# ADC_Input.net
KiCad netlist of a schematic drawn in Altium Designer
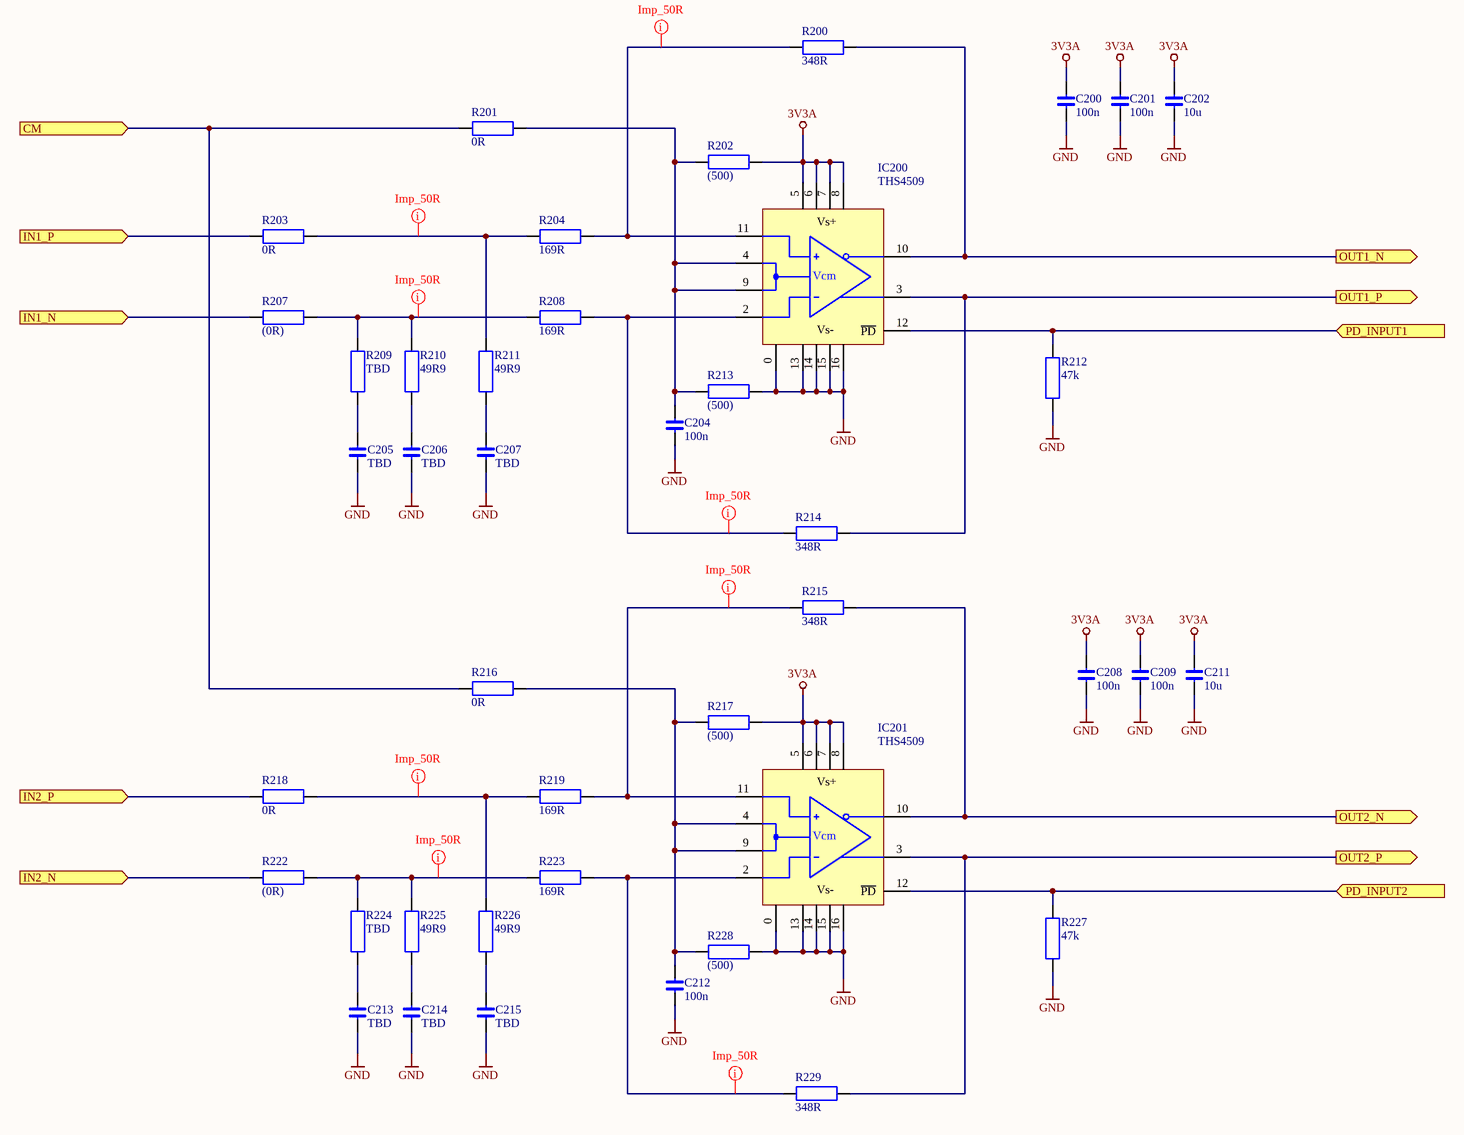
[diagram p0: ADC_Input.SchDoc]

(export (version "E")
  (design (tool "Eeschema 10.0.6"))
  (components
    (comp (ref "C200")
      (value "100n")
      (footprint "0603 SMALL OUTLINE")
      (description "C")
      (libsource (lib "RCL") (part "C"))
    )
    (comp (ref "C201")
      (value "100n")
      (footprint "0603 SMALL OUTLINE")
      (description "C")
      (libsource (lib "RCL") (part "C"))
    )
    (comp (ref "C202")
      (value "10u")
      (footprint "0805 SMALL OUTLINE")
      (description "C")
      (libsource (lib "RCL") (part "C"))
    )
    (comp (ref "C204")
      (value "100n")
      (footprint "0603 SMALL OUTLINE")
      (description "C")
      (libsource (lib "RCL") (part "C"))
    )
    (comp (ref "C205")
      (value "TBD")
      (footprint "0603 SMALL OUTLINE")
      (description "C")
      (libsource (lib "RCL") (part "C"))
    )
    (comp (ref "C206")
      (value "TBD")
      (footprint "0603 SMALL OUTLINE")
      (description "C")
      (libsource (lib "RCL") (part "C"))
    )
    (comp (ref "C207")
      (value "TBD")
      (footprint "0603 SMALL OUTLINE")
      (description "C")
      (libsource (lib "RCL") (part "C"))
    )
    (comp (ref "C208")
      (value "100n")
      (footprint "0603 SMALL OUTLINE")
      (description "C")
      (libsource (lib "RCL") (part "C"))
    )
    (comp (ref "C209")
      (value "100n")
      (footprint "0603 SMALL OUTLINE")
      (description "C")
      (libsource (lib "RCL") (part "C"))
    )
    (comp (ref "C211")
      (value "10u")
      (footprint "0805 SMALL OUTLINE")
      (description "C")
      (libsource (lib "RCL") (part "C"))
    )
    (comp (ref "C212")
      (value "100n")
      (footprint "0603 SMALL OUTLINE")
      (description "C")
      (libsource (lib "RCL") (part "C"))
    )
    (comp (ref "C213")
      (value "TBD")
      (footprint "0603 SMALL OUTLINE")
      (description "C")
      (libsource (lib "RCL") (part "C"))
    )
    (comp (ref "C214")
      (value "TBD")
      (footprint "0603 SMALL OUTLINE")
      (description "C")
      (libsource (lib "RCL") (part "C"))
    )
    (comp (ref "C215")
      (value "TBD")
      (footprint "0603 SMALL OUTLINE")
      (description "C")
      (libsource (lib "RCL") (part "C"))
    )
    (comp (ref "IC200")
      (value "THS4509")
      (footprint "QFN16_LONG")
      (description "WIDEBAND, LOW-NOISE, LOW-DISTORTION, FULLY-DIFFERENTIAL AMPLIFIER")
      (libsource (lib "Private") (part "THS4509"))
    )
    (comp (ref "IC201")
      (value "THS4509")
      (footprint "QFN16_LONG")
      (description "WIDEBAND, LOW-NOISE, LOW-DISTORTION, FULLY-DIFFERENTIAL AMPLIFIER")
      (libsource (lib "Private") (part "THS4509"))
    )
    (comp (ref "R200")
      (value "348R")
      (footprint "0603 SMALL OUTLINE")
      (description "R")
      (libsource (lib "RCL") (part "R"))
    )
    (comp (ref "R201")
      (value "0R")
      (footprint "0603 SMALL OUTLINE")
      (description "R")
      (libsource (lib "RCL") (part "R"))
    )
    (comp (ref "R202")
      (value "(500)")
      (footprint "0603 SMALL OUTLINE")
      (description "R")
      (libsource (lib "RCL") (part "R"))
    )
    (comp (ref "R203")
      (value "0R")
      (footprint "0603 SMALL OUTLINE")
      (description "R")
      (libsource (lib "RCL") (part "R"))
    )
    (comp (ref "R204")
      (value "169R")
      (footprint "0603 SMALL OUTLINE")
      (description "R")
      (libsource (lib "RCL") (part "R"))
    )
    (comp (ref "R207")
      (value "(0R)")
      (footprint "0603 SMALL OUTLINE")
      (description "R")
      (libsource (lib "RCL") (part "R"))
    )
    (comp (ref "R208")
      (value "169R")
      (footprint "0603 SMALL OUTLINE")
      (description "R")
      (libsource (lib "RCL") (part "R"))
    )
    (comp (ref "R209")
      (value "TBD")
      (footprint "0603 SMALL OUTLINE")
      (description "R")
      (libsource (lib "RCL") (part "R"))
    )
    (comp (ref "R210")
      (value "49R9")
      (footprint "0603 SMALL OUTLINE")
      (description "R")
      (libsource (lib "RCL") (part "R"))
    )
    (comp (ref "R211")
      (value "49R9")
      (footprint "0603 SMALL OUTLINE")
      (description "R")
      (libsource (lib "RCL") (part "R"))
    )
    (comp (ref "R212")
      (value "47k")
      (footprint "0603 SMALL OUTLINE")
      (description "R")
      (libsource (lib "RCL") (part "R"))
    )
    (comp (ref "R213")
      (value "(500)")
      (footprint "0603 SMALL OUTLINE")
      (description "R")
      (libsource (lib "RCL") (part "R"))
    )
    (comp (ref "R214")
      (value "348R")
      (footprint "0603 SMALL OUTLINE")
      (description "R")
      (libsource (lib "RCL") (part "R"))
    )
    (comp (ref "R215")
      (value "348R")
      (footprint "0603 SMALL OUTLINE")
      (description "R")
      (libsource (lib "RCL") (part "R"))
    )
    (comp (ref "R216")
      (value "0R")
      (footprint "0603 SMALL OUTLINE")
      (description "R")
      (libsource (lib "RCL") (part "R"))
    )
    (comp (ref "R217")
      (value "(500)")
      (footprint "0603 SMALL OUTLINE")
      (description "R")
      (libsource (lib "RCL") (part "R"))
    )
    (comp (ref "R218")
      (value "0R")
      (footprint "0603 SMALL OUTLINE")
      (description "R")
      (libsource (lib "RCL") (part "R"))
    )
    (comp (ref "R219")
      (value "169R")
      (footprint "0603 SMALL OUTLINE")
      (description "R")
      (libsource (lib "RCL") (part "R"))
    )
    (comp (ref "R222")
      (value "(0R)")
      (footprint "0603 SMALL OUTLINE")
      (description "R")
      (libsource (lib "RCL") (part "R"))
    )
    (comp (ref "R223")
      (value "169R")
      (footprint "0603 SMALL OUTLINE")
      (description "R")
      (libsource (lib "RCL") (part "R"))
    )
    (comp (ref "R224")
      (value "TBD")
      (footprint "0603 SMALL OUTLINE")
      (description "R")
      (libsource (lib "RCL") (part "R"))
    )
    (comp (ref "R225")
      (value "49R9")
      (footprint "0603 SMALL OUTLINE")
      (description "R")
      (libsource (lib "RCL") (part "R"))
    )
    (comp (ref "R226")
      (value "49R9")
      (footprint "0603 SMALL OUTLINE")
      (description "R")
      (libsource (lib "RCL") (part "R"))
    )
    (comp (ref "R227")
      (value "47k")
      (footprint "0603 SMALL OUTLINE")
      (description "R")
      (libsource (lib "RCL") (part "R"))
    )
    (comp (ref "R228")
      (value "(500)")
      (footprint "0603 SMALL OUTLINE")
      (description "R")
      (libsource (lib "RCL") (part "R"))
    )
    (comp (ref "R229")
      (value "348R")
      (footprint "0603 SMALL OUTLINE")
      (description "R")
      (libsource (lib "RCL") (part "R"))
    )
  )
  (nets
    (net (code "1") (name "/CM") (class "Default")
      (node (ref "R201") (pin "1") (pinfunction "1_1") (pintype "passive"))
      (node (ref "R216") (pin "1") (pinfunction "1_1") (pintype "passive"))
    )
    (net (code "2") (name "/IN1_N") (class "Default")
      (node (ref "R207") (pin "1") (pinfunction "1_1") (pintype "passive"))
    )
    (net (code "3") (name "/IN1_P") (class "Default")
      (node (ref "R203") (pin "1") (pinfunction "1_1") (pintype "passive"))
    )
    (net (code "4") (name "/IN2_N") (class "Default")
      (node (ref "R222") (pin "1") (pinfunction "1_1") (pintype "passive"))
    )
    (net (code "5") (name "/IN2_P") (class "Default")
      (node (ref "R218") (pin "1") (pinfunction "1_1") (pintype "passive"))
    )
    (net (code "6") (name "/OUT1_N") (class "Default")
      (node (ref "IC200") (pin "10") (pinfunction "-OUT_10") (pintype "passive"))
      (node (ref "R200") (pin "1") (pinfunction "1_1") (pintype "passive"))
    )
    (net (code "7") (name "/OUT1_P") (class "Default")
      (node (ref "IC200") (pin "3") (pinfunction "+OUT_3") (pintype "passive"))
      (node (ref "R214") (pin "1") (pinfunction "1_1") (pintype "passive"))
    )
    (net (code "8") (name "/OUT2_N") (class "Default")
      (node (ref "IC201") (pin "10") (pinfunction "-OUT_10") (pintype "passive"))
      (node (ref "R215") (pin "1") (pinfunction "1_1") (pintype "passive"))
    )
    (net (code "9") (name "/OUT2_P") (class "Default")
      (node (ref "IC201") (pin "3") (pinfunction "+OUT_3") (pintype "passive"))
      (node (ref "R229") (pin "1") (pinfunction "1_1") (pintype "passive"))
    )
    (net (code "10") (name "/PD_INPUT1") (class "Default")
      (node (ref "IC200") (pin "12") (pinfunction "~{PD}_12") (pintype "passive"))
      (node (ref "R212") (pin "2") (pinfunction "2_2") (pintype "passive"))
    )
    (net (code "11") (name "/PD_INPUT2") (class "Default")
      (node (ref "IC201") (pin "12") (pinfunction "~{PD}_12") (pintype "passive"))
      (node (ref "R227") (pin "2") (pinfunction "2_2") (pintype "passive"))
    )
    (net (code "12") (name "3V3A") (class "Default")
      (node (ref "C200") (pin "1") (pinfunction "1_1") (pintype "passive"))
      (node (ref "C201") (pin "1") (pinfunction "1_1") (pintype "passive"))
      (node (ref "C202") (pin "1") (pinfunction "1_1") (pintype "passive"))
      (node (ref "C208") (pin "1") (pinfunction "1_1") (pintype "passive"))
      (node (ref "C209") (pin "1") (pinfunction "1_1") (pintype "passive"))
      (node (ref "C211") (pin "1") (pinfunction "1_1") (pintype "passive"))
      (node (ref "IC200") (pin "5") (pinfunction "Vs+_5") (pintype "passive"))
      (node (ref "IC200") (pin "6") (pinfunction "Vs+_6") (pintype "passive"))
      (node (ref "IC200") (pin "7") (pinfunction "Vs+_7") (pintype "passive"))
      (node (ref "IC200") (pin "8") (pinfunction "Vs+_8") (pintype "passive"))
      (node (ref "IC201") (pin "5") (pinfunction "Vs+_5") (pintype "passive"))
      (node (ref "IC201") (pin "6") (pinfunction "Vs+_6") (pintype "passive"))
      (node (ref "IC201") (pin "7") (pinfunction "Vs+_7") (pintype "passive"))
      (node (ref "IC201") (pin "8") (pinfunction "Vs+_8") (pintype "passive"))
      (node (ref "R202") (pin "1") (pinfunction "1_1") (pintype "passive"))
      (node (ref "R217") (pin "1") (pinfunction "1_1") (pintype "passive"))
    )
    (net (code "13") (name "GND") (class "Default")
      (node (ref "C200") (pin "2") (pinfunction "2_2") (pintype "passive"))
      (node (ref "C201") (pin "2") (pinfunction "2_2") (pintype "passive"))
      (node (ref "C202") (pin "2") (pinfunction "2_2") (pintype "passive"))
      (node (ref "C204") (pin "2") (pinfunction "2_2") (pintype "passive"))
      (node (ref "C205") (pin "2") (pinfunction "2_2") (pintype "passive"))
      (node (ref "C206") (pin "2") (pinfunction "2_2") (pintype "passive"))
      (node (ref "C207") (pin "2") (pinfunction "2_2") (pintype "passive"))
      (node (ref "C208") (pin "2") (pinfunction "2_2") (pintype "passive"))
      (node (ref "C209") (pin "2") (pinfunction "2_2") (pintype "passive"))
      (node (ref "C211") (pin "2") (pinfunction "2_2") (pintype "passive"))
      (node (ref "C212") (pin "2") (pinfunction "2_2") (pintype "passive"))
      (node (ref "C213") (pin "2") (pinfunction "2_2") (pintype "passive"))
      (node (ref "C214") (pin "2") (pinfunction "2_2") (pintype "passive"))
      (node (ref "C215") (pin "2") (pinfunction "2_2") (pintype "passive"))
      (node (ref "IC200") (pin "0") (pinfunction "PAD_0") (pintype "passive"))
      (node (ref "IC200") (pin "13") (pinfunction "Vs-_13") (pintype "passive"))
      (node (ref "IC200") (pin "14") (pinfunction "Vs-_14") (pintype "passive"))
      (node (ref "IC200") (pin "15") (pinfunction "Vs-_15") (pintype "passive"))
      (node (ref "IC200") (pin "16") (pinfunction "Vs-_16") (pintype "passive"))
      (node (ref "IC201") (pin "0") (pinfunction "PAD_0") (pintype "passive"))
      (node (ref "IC201") (pin "13") (pinfunction "Vs-_13") (pintype "passive"))
      (node (ref "IC201") (pin "14") (pinfunction "Vs-_14") (pintype "passive"))
      (node (ref "IC201") (pin "15") (pinfunction "Vs-_15") (pintype "passive"))
      (node (ref "IC201") (pin "16") (pinfunction "Vs-_16") (pintype "passive"))
      (node (ref "R212") (pin "1") (pinfunction "1_1") (pintype "passive"))
      (node (ref "R213") (pin "1") (pinfunction "1_1") (pintype "passive"))
      (node (ref "R227") (pin "1") (pinfunction "1_1") (pintype "passive"))
      (node (ref "R228") (pin "1") (pinfunction "1_1") (pintype "passive"))
    )
    (net (code "14") (name "Net-(C204-Pad1)") (class "Default")
      (node (ref "C204") (pin "1") (pinfunction "1_1") (pintype "passive"))
      (node (ref "IC200") (pin "4") (pinfunction "CM_4") (pintype "passive"))
      (node (ref "IC200") (pin "9") (pinfunction "CM_9") (pintype "passive"))
      (node (ref "R201") (pin "2") (pinfunction "2_2") (pintype "passive"))
      (node (ref "R202") (pin "2") (pinfunction "2_2") (pintype "passive"))
      (node (ref "R213") (pin "2") (pinfunction "2_2") (pintype "passive"))
    )
    (net (code "15") (name "Net-(C205-Pad1)") (class "Default")
      (node (ref "C205") (pin "1") (pinfunction "1_1") (pintype "passive"))
      (node (ref "R209") (pin "1") (pinfunction "1_1") (pintype "passive"))
    )
    (net (code "16") (name "Net-(C206-Pad1)") (class "Default")
      (node (ref "C206") (pin "1") (pinfunction "1_1") (pintype "passive"))
      (node (ref "R210") (pin "1") (pinfunction "1_1") (pintype "passive"))
    )
    (net (code "17") (name "Net-(C207-Pad1)") (class "Default")
      (node (ref "C207") (pin "1") (pinfunction "1_1") (pintype "passive"))
      (node (ref "R211") (pin "1") (pinfunction "1_1") (pintype "passive"))
    )
    (net (code "18") (name "Net-(C212-Pad1)") (class "Default")
      (node (ref "C212") (pin "1") (pinfunction "1_1") (pintype "passive"))
      (node (ref "IC201") (pin "4") (pinfunction "CM_4") (pintype "passive"))
      (node (ref "IC201") (pin "9") (pinfunction "CM_9") (pintype "passive"))
      (node (ref "R216") (pin "2") (pinfunction "2_2") (pintype "passive"))
      (node (ref "R217") (pin "2") (pinfunction "2_2") (pintype "passive"))
      (node (ref "R228") (pin "2") (pinfunction "2_2") (pintype "passive"))
    )
    (net (code "19") (name "Net-(C213-Pad1)") (class "Default")
      (node (ref "C213") (pin "1") (pinfunction "1_1") (pintype "passive"))
      (node (ref "R224") (pin "1") (pinfunction "1_1") (pintype "passive"))
    )
    (net (code "20") (name "Net-(C214-Pad1)") (class "Default")
      (node (ref "C214") (pin "1") (pinfunction "1_1") (pintype "passive"))
      (node (ref "R225") (pin "1") (pinfunction "1_1") (pintype "passive"))
    )
    (net (code "21") (name "Net-(C215-Pad1)") (class "Default")
      (node (ref "C215") (pin "1") (pinfunction "1_1") (pintype "passive"))
      (node (ref "R226") (pin "1") (pinfunction "1_1") (pintype "passive"))
    )
    (net (code "22") (name "Net-(IC200-+IN)") (class "Default")
      (node (ref "IC200") (pin "11") (pinfunction "+IN_11") (pintype "passive"))
      (node (ref "R200") (pin "2") (pinfunction "2_2") (pintype "passive"))
      (node (ref "R204") (pin "1") (pinfunction "1_1") (pintype "passive"))
    )
    (net (code "23") (name "Net-(IC200--IN)") (class "Default")
      (node (ref "IC200") (pin "2") (pinfunction "-IN_2") (pintype "passive"))
      (node (ref "R208") (pin "1") (pinfunction "1_1") (pintype "passive"))
      (node (ref "R214") (pin "2") (pinfunction "2_2") (pintype "passive"))
    )
    (net (code "24") (name "Net-(IC201-+IN)") (class "Default")
      (node (ref "IC201") (pin "11") (pinfunction "+IN_11") (pintype "passive"))
      (node (ref "R215") (pin "2") (pinfunction "2_2") (pintype "passive"))
      (node (ref "R219") (pin "1") (pinfunction "1_1") (pintype "passive"))
    )
    (net (code "25") (name "Net-(IC201--IN)") (class "Default")
      (node (ref "IC201") (pin "2") (pinfunction "-IN_2") (pintype "passive"))
      (node (ref "R223") (pin "1") (pinfunction "1_1") (pintype "passive"))
      (node (ref "R229") (pin "2") (pinfunction "2_2") (pintype "passive"))
    )
    (net (code "26") (name "Net-(R203-Pad2)") (class "Default")
      (node (ref "R203") (pin "2") (pinfunction "2_2") (pintype "passive"))
      (node (ref "R204") (pin "2") (pinfunction "2_2") (pintype "passive"))
      (node (ref "R211") (pin "2") (pinfunction "2_2") (pintype "passive"))
    )
    (net (code "27") (name "Net-(R207-Pad2)") (class "Default")
      (node (ref "R207") (pin "2") (pinfunction "2_2") (pintype "passive"))
      (node (ref "R208") (pin "2") (pinfunction "2_2") (pintype "passive"))
      (node (ref "R209") (pin "2") (pinfunction "2_2") (pintype "passive"))
      (node (ref "R210") (pin "2") (pinfunction "2_2") (pintype "passive"))
    )
    (net (code "28") (name "Net-(R218-Pad2)") (class "Default")
      (node (ref "R218") (pin "2") (pinfunction "2_2") (pintype "passive"))
      (node (ref "R219") (pin "2") (pinfunction "2_2") (pintype "passive"))
      (node (ref "R226") (pin "2") (pinfunction "2_2") (pintype "passive"))
    )
    (net (code "29") (name "Net-(R222-Pad2)") (class "Default")
      (node (ref "R222") (pin "2") (pinfunction "2_2") (pintype "passive"))
      (node (ref "R223") (pin "2") (pinfunction "2_2") (pintype "passive"))
      (node (ref "R224") (pin "2") (pinfunction "2_2") (pintype "passive"))
      (node (ref "R225") (pin "2") (pinfunction "2_2") (pintype "passive"))
    )
  )
)
